# UV-Led.net
KiCad netlist of a schematic drawn in EAGLE
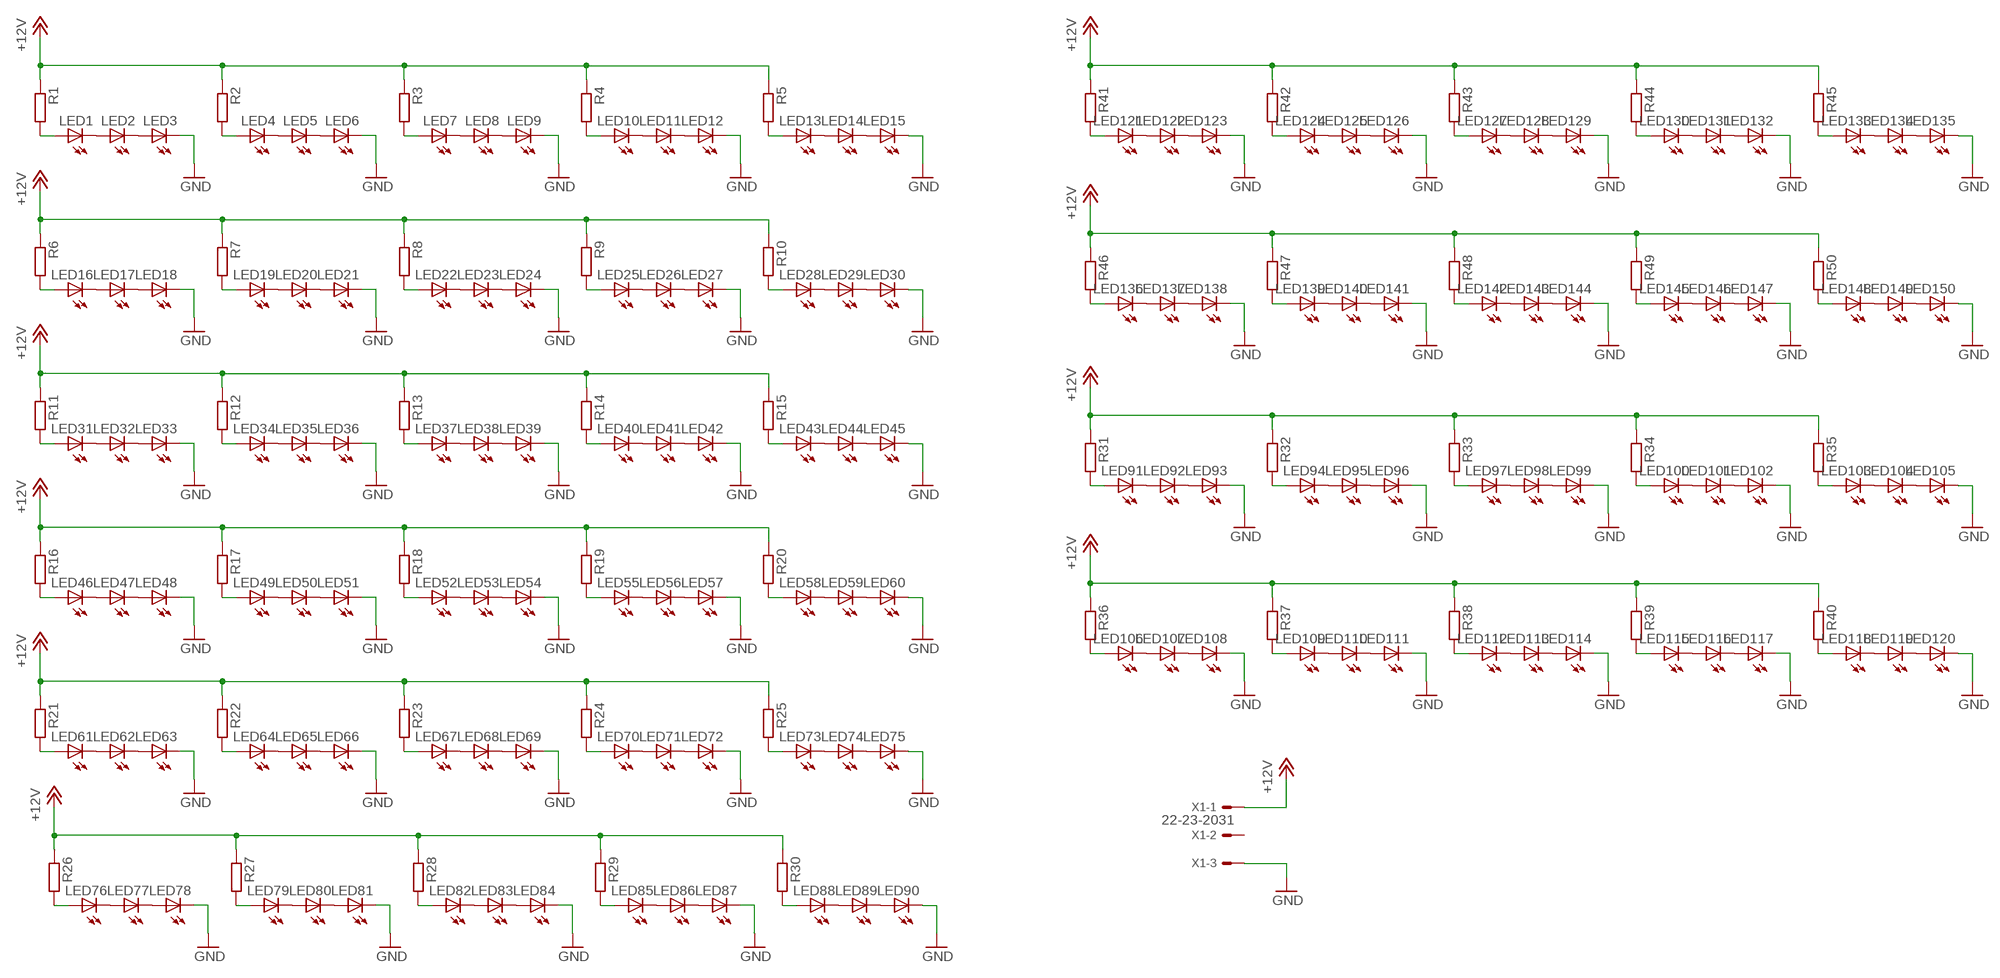
[diagram p0: schematic, sheet 1]

(export (version "E")
  (design (tool "Eeschema 10.0.6"))
  (components
    (comp (ref "LED1")
      (value "LED5MM")
      (footprint "eagle-import:LED5MM")
      (libsource (lib "eagle-import") (part "LED5MM"))
    )
    (comp (ref "LED2")
      (value "LED5MM")
      (footprint "eagle-import:LED5MM")
      (libsource (lib "eagle-import") (part "LED5MM"))
    )
    (comp (ref "LED3")
      (value "LED5MM")
      (footprint "eagle-import:LED5MM")
      (libsource (lib "eagle-import") (part "LED5MM"))
    )
    (comp (ref "LED4")
      (value "LED5MM")
      (footprint "eagle-import:LED5MM")
      (libsource (lib "eagle-import") (part "LED5MM"))
    )
    (comp (ref "LED5")
      (value "LED5MM")
      (footprint "eagle-import:LED5MM")
      (libsource (lib "eagle-import") (part "LED5MM"))
    )
    (comp (ref "LED6")
      (value "LED5MM")
      (footprint "eagle-import:LED5MM")
      (libsource (lib "eagle-import") (part "LED5MM"))
    )
    (comp (ref "LED7")
      (value "LED5MM")
      (footprint "eagle-import:LED5MM")
      (libsource (lib "eagle-import") (part "LED5MM"))
    )
    (comp (ref "LED8")
      (value "LED5MM")
      (footprint "eagle-import:LED5MM")
      (libsource (lib "eagle-import") (part "LED5MM"))
    )
    (comp (ref "LED9")
      (value "LED5MM")
      (footprint "eagle-import:LED5MM")
      (libsource (lib "eagle-import") (part "LED5MM"))
    )
    (comp (ref "LED10")
      (value "LED5MM")
      (footprint "eagle-import:LED5MM")
      (libsource (lib "eagle-import") (part "LED5MM"))
    )
    (comp (ref "LED11")
      (value "LED5MM")
      (footprint "eagle-import:LED5MM")
      (libsource (lib "eagle-import") (part "LED5MM"))
    )
    (comp (ref "LED12")
      (value "LED5MM")
      (footprint "eagle-import:LED5MM")
      (libsource (lib "eagle-import") (part "LED5MM"))
    )
    (comp (ref "LED13")
      (value "LED5MM")
      (footprint "eagle-import:LED5MM")
      (libsource (lib "eagle-import") (part "LED5MM"))
    )
    (comp (ref "LED14")
      (value "LED5MM")
      (footprint "eagle-import:LED5MM")
      (libsource (lib "eagle-import") (part "LED5MM"))
    )
    (comp (ref "LED15")
      (value "LED5MM")
      (footprint "eagle-import:LED5MM")
      (libsource (lib "eagle-import") (part "LED5MM"))
    )
    (comp (ref "LED16")
      (value "LED5MM")
      (footprint "eagle-import:LED5MM")
      (libsource (lib "eagle-import") (part "LED5MM"))
    )
    (comp (ref "LED17")
      (value "LED5MM")
      (footprint "eagle-import:LED5MM")
      (libsource (lib "eagle-import") (part "LED5MM"))
    )
    (comp (ref "LED18")
      (value "LED5MM")
      (footprint "eagle-import:LED5MM")
      (libsource (lib "eagle-import") (part "LED5MM"))
    )
    (comp (ref "LED19")
      (value "LED5MM")
      (footprint "eagle-import:LED5MM")
      (libsource (lib "eagle-import") (part "LED5MM"))
    )
    (comp (ref "LED20")
      (value "LED5MM")
      (footprint "eagle-import:LED5MM")
      (libsource (lib "eagle-import") (part "LED5MM"))
    )
    (comp (ref "LED21")
      (value "LED5MM")
      (footprint "eagle-import:LED5MM")
      (libsource (lib "eagle-import") (part "LED5MM"))
    )
    (comp (ref "LED22")
      (value "LED5MM")
      (footprint "eagle-import:LED5MM")
      (libsource (lib "eagle-import") (part "LED5MM"))
    )
    (comp (ref "LED23")
      (value "LED5MM")
      (footprint "eagle-import:LED5MM")
      (libsource (lib "eagle-import") (part "LED5MM"))
    )
    (comp (ref "LED24")
      (value "LED5MM")
      (footprint "eagle-import:LED5MM")
      (libsource (lib "eagle-import") (part "LED5MM"))
    )
    (comp (ref "LED25")
      (value "LED5MM")
      (footprint "eagle-import:LED5MM")
      (libsource (lib "eagle-import") (part "LED5MM"))
    )
    (comp (ref "LED26")
      (value "LED5MM")
      (footprint "eagle-import:LED5MM")
      (libsource (lib "eagle-import") (part "LED5MM"))
    )
    (comp (ref "LED27")
      (value "LED5MM")
      (footprint "eagle-import:LED5MM")
      (libsource (lib "eagle-import") (part "LED5MM"))
    )
    (comp (ref "LED28")
      (value "LED5MM")
      (footprint "eagle-import:LED5MM")
      (libsource (lib "eagle-import") (part "LED5MM"))
    )
    (comp (ref "LED29")
      (value "LED5MM")
      (footprint "eagle-import:LED5MM")
      (libsource (lib "eagle-import") (part "LED5MM"))
    )
    (comp (ref "LED30")
      (value "LED5MM")
      (footprint "eagle-import:LED5MM")
      (libsource (lib "eagle-import") (part "LED5MM"))
    )
    (comp (ref "LED31")
      (value "LED5MM")
      (footprint "eagle-import:LED5MM")
      (libsource (lib "eagle-import") (part "LED5MM"))
    )
    (comp (ref "LED32")
      (value "LED5MM")
      (footprint "eagle-import:LED5MM")
      (libsource (lib "eagle-import") (part "LED5MM"))
    )
    (comp (ref "LED33")
      (value "LED5MM")
      (footprint "eagle-import:LED5MM")
      (libsource (lib "eagle-import") (part "LED5MM"))
    )
    (comp (ref "LED34")
      (value "LED5MM")
      (footprint "eagle-import:LED5MM")
      (libsource (lib "eagle-import") (part "LED5MM"))
    )
    (comp (ref "LED35")
      (value "LED5MM")
      (footprint "eagle-import:LED5MM")
      (libsource (lib "eagle-import") (part "LED5MM"))
    )
    (comp (ref "LED36")
      (value "LED5MM")
      (footprint "eagle-import:LED5MM")
      (libsource (lib "eagle-import") (part "LED5MM"))
    )
    (comp (ref "LED37")
      (value "LED5MM")
      (footprint "eagle-import:LED5MM")
      (libsource (lib "eagle-import") (part "LED5MM"))
    )
    (comp (ref "LED38")
      (value "LED5MM")
      (footprint "eagle-import:LED5MM")
      (libsource (lib "eagle-import") (part "LED5MM"))
    )
    (comp (ref "LED39")
      (value "LED5MM")
      (footprint "eagle-import:LED5MM")
      (libsource (lib "eagle-import") (part "LED5MM"))
    )
    (comp (ref "LED40")
      (value "LED5MM")
      (footprint "eagle-import:LED5MM")
      (libsource (lib "eagle-import") (part "LED5MM"))
    )
    (comp (ref "LED41")
      (value "LED5MM")
      (footprint "eagle-import:LED5MM")
      (libsource (lib "eagle-import") (part "LED5MM"))
    )
    (comp (ref "LED42")
      (value "LED5MM")
      (footprint "eagle-import:LED5MM")
      (libsource (lib "eagle-import") (part "LED5MM"))
    )
    (comp (ref "LED43")
      (value "LED5MM")
      (footprint "eagle-import:LED5MM")
      (libsource (lib "eagle-import") (part "LED5MM"))
    )
    (comp (ref "LED44")
      (value "LED5MM")
      (footprint "eagle-import:LED5MM")
      (libsource (lib "eagle-import") (part "LED5MM"))
    )
    (comp (ref "LED45")
      (value "LED5MM")
      (footprint "eagle-import:LED5MM")
      (libsource (lib "eagle-import") (part "LED5MM"))
    )
    (comp (ref "LED46")
      (value "LED5MM")
      (footprint "eagle-import:LED5MM")
      (libsource (lib "eagle-import") (part "LED5MM"))
    )
    (comp (ref "LED47")
      (value "LED5MM")
      (footprint "eagle-import:LED5MM")
      (libsource (lib "eagle-import") (part "LED5MM"))
    )
    (comp (ref "LED48")
      (value "LED5MM")
      (footprint "eagle-import:LED5MM")
      (libsource (lib "eagle-import") (part "LED5MM"))
    )
    (comp (ref "LED49")
      (value "LED5MM")
      (footprint "eagle-import:LED5MM")
      (libsource (lib "eagle-import") (part "LED5MM"))
    )
    (comp (ref "LED50")
      (value "LED5MM")
      (footprint "eagle-import:LED5MM")
      (libsource (lib "eagle-import") (part "LED5MM"))
    )
    (comp (ref "LED51")
      (value "LED5MM")
      (footprint "eagle-import:LED5MM")
      (libsource (lib "eagle-import") (part "LED5MM"))
    )
    (comp (ref "LED52")
      (value "LED5MM")
      (footprint "eagle-import:LED5MM")
      (libsource (lib "eagle-import") (part "LED5MM"))
    )
    (comp (ref "LED53")
      (value "LED5MM")
      (footprint "eagle-import:LED5MM")
      (libsource (lib "eagle-import") (part "LED5MM"))
    )
    (comp (ref "LED54")
      (value "LED5MM")
      (footprint "eagle-import:LED5MM")
      (libsource (lib "eagle-import") (part "LED5MM"))
    )
    (comp (ref "LED55")
      (value "LED5MM")
      (footprint "eagle-import:LED5MM")
      (libsource (lib "eagle-import") (part "LED5MM"))
    )
    (comp (ref "LED56")
      (value "LED5MM")
      (footprint "eagle-import:LED5MM")
      (libsource (lib "eagle-import") (part "LED5MM"))
    )
    (comp (ref "LED57")
      (value "LED5MM")
      (footprint "eagle-import:LED5MM")
      (libsource (lib "eagle-import") (part "LED5MM"))
    )
    (comp (ref "LED58")
      (value "LED5MM")
      (footprint "eagle-import:LED5MM")
      (libsource (lib "eagle-import") (part "LED5MM"))
    )
    (comp (ref "LED59")
      (value "LED5MM")
      (footprint "eagle-import:LED5MM")
      (libsource (lib "eagle-import") (part "LED5MM"))
    )
    (comp (ref "LED60")
      (value "LED5MM")
      (footprint "eagle-import:LED5MM")
      (libsource (lib "eagle-import") (part "LED5MM"))
    )
    (comp (ref "LED61")
      (value "LED5MM")
      (footprint "eagle-import:LED5MM")
      (libsource (lib "eagle-import") (part "LED5MM"))
    )
    (comp (ref "LED62")
      (value "LED5MM")
      (footprint "eagle-import:LED5MM")
      (libsource (lib "eagle-import") (part "LED5MM"))
    )
    (comp (ref "LED63")
      (value "LED5MM")
      (footprint "eagle-import:LED5MM")
      (libsource (lib "eagle-import") (part "LED5MM"))
    )
    (comp (ref "LED64")
      (value "LED5MM")
      (footprint "eagle-import:LED5MM")
      (libsource (lib "eagle-import") (part "LED5MM"))
    )
    (comp (ref "LED65")
      (value "LED5MM")
      (footprint "eagle-import:LED5MM")
      (libsource (lib "eagle-import") (part "LED5MM"))
    )
    (comp (ref "LED66")
      (value "LED5MM")
      (footprint "eagle-import:LED5MM")
      (libsource (lib "eagle-import") (part "LED5MM"))
    )
    (comp (ref "LED67")
      (value "LED5MM")
      (footprint "eagle-import:LED5MM")
      (libsource (lib "eagle-import") (part "LED5MM"))
    )
    (comp (ref "LED68")
      (value "LED5MM")
      (footprint "eagle-import:LED5MM")
      (libsource (lib "eagle-import") (part "LED5MM"))
    )
    (comp (ref "LED69")
      (value "LED5MM")
      (footprint "eagle-import:LED5MM")
      (libsource (lib "eagle-import") (part "LED5MM"))
    )
    (comp (ref "LED70")
      (value "LED5MM")
      (footprint "eagle-import:LED5MM")
      (libsource (lib "eagle-import") (part "LED5MM"))
    )
    (comp (ref "LED71")
      (value "LED5MM")
      (footprint "eagle-import:LED5MM")
      (libsource (lib "eagle-import") (part "LED5MM"))
    )
    (comp (ref "LED72")
      (value "LED5MM")
      (footprint "eagle-import:LED5MM")
      (libsource (lib "eagle-import") (part "LED5MM"))
    )
    (comp (ref "LED73")
      (value "LED5MM")
      (footprint "eagle-import:LED5MM")
      (libsource (lib "eagle-import") (part "LED5MM"))
    )
    (comp (ref "LED74")
      (value "LED5MM")
      (footprint "eagle-import:LED5MM")
      (libsource (lib "eagle-import") (part "LED5MM"))
    )
    (comp (ref "LED75")
      (value "LED5MM")
      (footprint "eagle-import:LED5MM")
      (libsource (lib "eagle-import") (part "LED5MM"))
    )
    (comp (ref "LED76")
      (value "LED5MM")
      (footprint "eagle-import:LED5MM")
      (libsource (lib "eagle-import") (part "LED5MM"))
    )
    (comp (ref "LED77")
      (value "LED5MM")
      (footprint "eagle-import:LED5MM")
      (libsource (lib "eagle-import") (part "LED5MM"))
    )
    (comp (ref "LED78")
      (value "LED5MM")
      (footprint "eagle-import:LED5MM")
      (libsource (lib "eagle-import") (part "LED5MM"))
    )
    (comp (ref "LED79")
      (value "LED5MM")
      (footprint "eagle-import:LED5MM")
      (libsource (lib "eagle-import") (part "LED5MM"))
    )
    (comp (ref "LED80")
      (value "LED5MM")
      (footprint "eagle-import:LED5MM")
      (libsource (lib "eagle-import") (part "LED5MM"))
    )
    (comp (ref "LED81")
      (value "LED5MM")
      (footprint "eagle-import:LED5MM")
      (libsource (lib "eagle-import") (part "LED5MM"))
    )
    (comp (ref "LED82")
      (value "LED5MM")
      (footprint "eagle-import:LED5MM")
      (libsource (lib "eagle-import") (part "LED5MM"))
    )
    (comp (ref "LED83")
      (value "LED5MM")
      (footprint "eagle-import:LED5MM")
      (libsource (lib "eagle-import") (part "LED5MM"))
    )
    (comp (ref "LED84")
      (value "LED5MM")
      (footprint "eagle-import:LED5MM")
      (libsource (lib "eagle-import") (part "LED5MM"))
    )
    (comp (ref "LED85")
      (value "LED5MM")
      (footprint "eagle-import:LED5MM")
      (libsource (lib "eagle-import") (part "LED5MM"))
    )
    (comp (ref "LED86")
      (value "LED5MM")
      (footprint "eagle-import:LED5MM")
      (libsource (lib "eagle-import") (part "LED5MM"))
    )
    (comp (ref "LED87")
      (value "LED5MM")
      (footprint "eagle-import:LED5MM")
      (libsource (lib "eagle-import") (part "LED5MM"))
    )
    (comp (ref "LED88")
      (value "LED5MM")
      (footprint "eagle-import:LED5MM")
      (libsource (lib "eagle-import") (part "LED5MM"))
    )
    (comp (ref "LED89")
      (value "LED5MM")
      (footprint "eagle-import:LED5MM")
      (libsource (lib "eagle-import") (part "LED5MM"))
    )
    (comp (ref "LED90")
      (value "LED5MM")
      (footprint "eagle-import:LED5MM")
      (libsource (lib "eagle-import") (part "LED5MM"))
    )
    (comp (ref "LED91")
      (value "LED5MM")
      (footprint "eagle-import:LED5MM")
      (libsource (lib "eagle-import") (part "LED5MM"))
    )
    (comp (ref "LED92")
      (value "LED5MM")
      (footprint "eagle-import:LED5MM")
      (libsource (lib "eagle-import") (part "LED5MM"))
    )
    (comp (ref "LED93")
      (value "LED5MM")
      (footprint "eagle-import:LED5MM")
      (libsource (lib "eagle-import") (part "LED5MM"))
    )
    (comp (ref "LED94")
      (value "LED5MM")
      (footprint "eagle-import:LED5MM")
      (libsource (lib "eagle-import") (part "LED5MM"))
    )
    (comp (ref "LED95")
      (value "LED5MM")
      (footprint "eagle-import:LED5MM")
      (libsource (lib "eagle-import") (part "LED5MM"))
    )
    (comp (ref "LED96")
      (value "LED5MM")
      (footprint "eagle-import:LED5MM")
      (libsource (lib "eagle-import") (part "LED5MM"))
    )
    (comp (ref "LED97")
      (value "LED5MM")
      (footprint "eagle-import:LED5MM")
      (libsource (lib "eagle-import") (part "LED5MM"))
    )
    (comp (ref "LED98")
      (value "LED5MM")
      (footprint "eagle-import:LED5MM")
      (libsource (lib "eagle-import") (part "LED5MM"))
    )
    (comp (ref "LED99")
      (value "LED5MM")
      (footprint "eagle-import:LED5MM")
      (libsource (lib "eagle-import") (part "LED5MM"))
    )
    (comp (ref "LED100")
      (value "LED5MM")
      (footprint "eagle-import:LED5MM")
      (libsource (lib "eagle-import") (part "LED5MM"))
    )
    (comp (ref "LED101")
      (value "LED5MM")
      (footprint "eagle-import:LED5MM")
      (libsource (lib "eagle-import") (part "LED5MM"))
    )
    (comp (ref "LED102")
      (value "LED5MM")
      (footprint "eagle-import:LED5MM")
      (libsource (lib "eagle-import") (part "LED5MM"))
    )
    (comp (ref "LED103")
      (value "LED5MM")
      (footprint "eagle-import:LED5MM")
      (libsource (lib "eagle-import") (part "LED5MM"))
    )
    (comp (ref "LED104")
      (value "LED5MM")
      (footprint "eagle-import:LED5MM")
      (libsource (lib "eagle-import") (part "LED5MM"))
    )
    (comp (ref "LED105")
      (value "LED5MM")
      (footprint "eagle-import:LED5MM")
      (libsource (lib "eagle-import") (part "LED5MM"))
    )
    (comp (ref "LED106")
      (value "LED5MM")
      (footprint "eagle-import:LED5MM")
      (libsource (lib "eagle-import") (part "LED5MM"))
    )
    (comp (ref "LED107")
      (value "LED5MM")
      (footprint "eagle-import:LED5MM")
      (libsource (lib "eagle-import") (part "LED5MM"))
    )
    (comp (ref "LED108")
      (value "LED5MM")
      (footprint "eagle-import:LED5MM")
      (libsource (lib "eagle-import") (part "LED5MM"))
    )
    (comp (ref "LED109")
      (value "LED5MM")
      (footprint "eagle-import:LED5MM")
      (libsource (lib "eagle-import") (part "LED5MM"))
    )
    (comp (ref "LED110")
      (value "LED5MM")
      (footprint "eagle-import:LED5MM")
      (libsource (lib "eagle-import") (part "LED5MM"))
    )
    (comp (ref "LED111")
      (value "LED5MM")
      (footprint "eagle-import:LED5MM")
      (libsource (lib "eagle-import") (part "LED5MM"))
    )
    (comp (ref "LED112")
      (value "LED5MM")
      (footprint "eagle-import:LED5MM")
      (libsource (lib "eagle-import") (part "LED5MM"))
    )
    (comp (ref "LED113")
      (value "LED5MM")
      (footprint "eagle-import:LED5MM")
      (libsource (lib "eagle-import") (part "LED5MM"))
    )
    (comp (ref "LED114")
      (value "LED5MM")
      (footprint "eagle-import:LED5MM")
      (libsource (lib "eagle-import") (part "LED5MM"))
    )
    (comp (ref "LED115")
      (value "LED5MM")
      (footprint "eagle-import:LED5MM")
      (libsource (lib "eagle-import") (part "LED5MM"))
    )
    (comp (ref "LED116")
      (value "LED5MM")
      (footprint "eagle-import:LED5MM")
      (libsource (lib "eagle-import") (part "LED5MM"))
    )
    (comp (ref "LED117")
      (value "LED5MM")
      (footprint "eagle-import:LED5MM")
      (libsource (lib "eagle-import") (part "LED5MM"))
    )
    (comp (ref "LED118")
      (value "LED5MM")
      (footprint "eagle-import:LED5MM")
      (libsource (lib "eagle-import") (part "LED5MM"))
    )
    (comp (ref "LED119")
      (value "LED5MM")
      (footprint "eagle-import:LED5MM")
      (libsource (lib "eagle-import") (part "LED5MM"))
    )
    (comp (ref "LED120")
      (value "LED5MM")
      (footprint "eagle-import:LED5MM")
      (libsource (lib "eagle-import") (part "LED5MM"))
    )
    (comp (ref "LED121")
      (value "LED5MM")
      (footprint "eagle-import:LED5MM")
      (libsource (lib "eagle-import") (part "LED5MM"))
    )
    (comp (ref "LED122")
      (value "LED5MM")
      (footprint "eagle-import:LED5MM")
      (libsource (lib "eagle-import") (part "LED5MM"))
    )
    (comp (ref "LED123")
      (value "LED5MM")
      (footprint "eagle-import:LED5MM")
      (libsource (lib "eagle-import") (part "LED5MM"))
    )
    (comp (ref "LED124")
      (value "LED5MM")
      (footprint "eagle-import:LED5MM")
      (libsource (lib "eagle-import") (part "LED5MM"))
    )
    (comp (ref "LED125")
      (value "LED5MM")
      (footprint "eagle-import:LED5MM")
      (libsource (lib "eagle-import") (part "LED5MM"))
    )
    (comp (ref "LED126")
      (value "LED5MM")
      (footprint "eagle-import:LED5MM")
      (libsource (lib "eagle-import") (part "LED5MM"))
    )
    (comp (ref "LED127")
      (value "LED5MM")
      (footprint "eagle-import:LED5MM")
      (libsource (lib "eagle-import") (part "LED5MM"))
    )
    (comp (ref "LED128")
      (value "LED5MM")
      (footprint "eagle-import:LED5MM")
      (libsource (lib "eagle-import") (part "LED5MM"))
    )
    (comp (ref "LED129")
      (value "LED5MM")
      (footprint "eagle-import:LED5MM")
      (libsource (lib "eagle-import") (part "LED5MM"))
    )
    (comp (ref "LED130")
      (value "LED5MM")
      (footprint "eagle-import:LED5MM")
      (libsource (lib "eagle-import") (part "LED5MM"))
    )
    (comp (ref "LED131")
      (value "LED5MM")
      (footprint "eagle-import:LED5MM")
      (libsource (lib "eagle-import") (part "LED5MM"))
    )
    (comp (ref "LED132")
      (value "LED5MM")
      (footprint "eagle-import:LED5MM")
      (libsource (lib "eagle-import") (part "LED5MM"))
    )
    (comp (ref "LED133")
      (value "LED5MM")
      (footprint "eagle-import:LED5MM")
      (libsource (lib "eagle-import") (part "LED5MM"))
    )
    (comp (ref "LED134")
      (value "LED5MM")
      (footprint "eagle-import:LED5MM")
      (libsource (lib "eagle-import") (part "LED5MM"))
    )
    (comp (ref "LED135")
      (value "LED5MM")
      (footprint "eagle-import:LED5MM")
      (libsource (lib "eagle-import") (part "LED5MM"))
    )
    (comp (ref "LED136")
      (value "LED5MM")
      (footprint "eagle-import:LED5MM")
      (libsource (lib "eagle-import") (part "LED5MM"))
    )
    (comp (ref "LED137")
      (value "LED5MM")
      (footprint "eagle-import:LED5MM")
      (libsource (lib "eagle-import") (part "LED5MM"))
    )
    (comp (ref "LED138")
      (value "LED5MM")
      (footprint "eagle-import:LED5MM")
      (libsource (lib "eagle-import") (part "LED5MM"))
    )
    (comp (ref "LED139")
      (value "LED5MM")
      (footprint "eagle-import:LED5MM")
      (libsource (lib "eagle-import") (part "LED5MM"))
    )
    (comp (ref "LED140")
      (value "LED5MM")
      (footprint "eagle-import:LED5MM")
      (libsource (lib "eagle-import") (part "LED5MM"))
    )
    (comp (ref "LED141")
      (value "LED5MM")
      (footprint "eagle-import:LED5MM")
      (libsource (lib "eagle-import") (part "LED5MM"))
    )
    (comp (ref "LED142")
      (value "LED5MM")
      (footprint "eagle-import:LED5MM")
      (libsource (lib "eagle-import") (part "LED5MM"))
    )
    (comp (ref "LED143")
      (value "LED5MM")
      (footprint "eagle-import:LED5MM")
      (libsource (lib "eagle-import") (part "LED5MM"))
    )
    (comp (ref "LED144")
      (value "LED5MM")
      (footprint "eagle-import:LED5MM")
      (libsource (lib "eagle-import") (part "LED5MM"))
    )
    (comp (ref "LED145")
      (value "LED5MM")
      (footprint "eagle-import:LED5MM")
      (libsource (lib "eagle-import") (part "LED5MM"))
    )
    (comp (ref "LED146")
      (value "LED5MM")
      (footprint "eagle-import:LED5MM")
      (libsource (lib "eagle-import") (part "LED5MM"))
    )
    (comp (ref "LED147")
      (value "LED5MM")
      (footprint "eagle-import:LED5MM")
      (libsource (lib "eagle-import") (part "LED5MM"))
    )
    (comp (ref "LED148")
      (value "LED5MM")
      (footprint "eagle-import:LED5MM")
      (libsource (lib "eagle-import") (part "LED5MM"))
    )
    (comp (ref "LED149")
      (value "LED5MM")
      (footprint "eagle-import:LED5MM")
      (libsource (lib "eagle-import") (part "LED5MM"))
    )
    (comp (ref "LED150")
      (value "LED5MM")
      (footprint "eagle-import:LED5MM")
      (libsource (lib "eagle-import") (part "LED5MM"))
    )
    (comp (ref "R1")
      (value "R-EU_0207/10")
      (footprint "eagle-import:0207_10")
      (libsource (lib "eagle-import") (part "R-EU_0207/10"))
    )
    (comp (ref "R2")
      (value "R-EU_0207/10")
      (footprint "eagle-import:0207_10")
      (libsource (lib "eagle-import") (part "R-EU_0207/10"))
    )
    (comp (ref "R3")
      (value "R-EU_0207/10")
      (footprint "eagle-import:0207_10")
      (libsource (lib "eagle-import") (part "R-EU_0207/10"))
    )
    (comp (ref "R4")
      (value "R-EU_0207/10")
      (footprint "eagle-import:0207_10")
      (libsource (lib "eagle-import") (part "R-EU_0207/10"))
    )
    (comp (ref "R5")
      (value "R-EU_0207/10")
      (footprint "eagle-import:0207_10")
      (libsource (lib "eagle-import") (part "R-EU_0207/10"))
    )
    (comp (ref "R6")
      (value "R-EU_0207/10")
      (footprint "eagle-import:0207_10")
      (libsource (lib "eagle-import") (part "R-EU_0207/10"))
    )
    (comp (ref "R7")
      (value "R-EU_0207/10")
      (footprint "eagle-import:0207_10")
      (libsource (lib "eagle-import") (part "R-EU_0207/10"))
    )
    (comp (ref "R8")
      (value "R-EU_0207/10")
      (footprint "eagle-import:0207_10")
      (libsource (lib "eagle-import") (part "R-EU_0207/10"))
    )
    (comp (ref "R9")
      (value "R-EU_0207/10")
      (footprint "eagle-import:0207_10")
      (libsource (lib "eagle-import") (part "R-EU_0207/10"))
    )
    (comp (ref "R10")
      (value "R-EU_0207/10")
      (footprint "eagle-import:0207_10")
      (libsource (lib "eagle-import") (part "R-EU_0207/10"))
    )
    (comp (ref "R11")
      (value "R-EU_0207/10")
      (footprint "eagle-import:0207_10")
      (libsource (lib "eagle-import") (part "R-EU_0207/10"))
    )
    (comp (ref "R12")
      (value "R-EU_0207/10")
      (footprint "eagle-import:0207_10")
      (libsource (lib "eagle-import") (part "R-EU_0207/10"))
    )
    (comp (ref "R13")
      (value "R-EU_0207/10")
      (footprint "eagle-import:0207_10")
      (libsource (lib "eagle-import") (part "R-EU_0207/10"))
    )
    (comp (ref "R14")
      (value "R-EU_0207/10")
      (footprint "eagle-import:0207_10")
      (libsource (lib "eagle-import") (part "R-EU_0207/10"))
    )
    (comp (ref "R15")
      (value "R-EU_0207/10")
      (footprint "eagle-import:0207_10")
      (libsource (lib "eagle-import") (part "R-EU_0207/10"))
    )
    (comp (ref "R16")
      (value "R-EU_0207/10")
      (footprint "eagle-import:0207_10")
      (libsource (lib "eagle-import") (part "R-EU_0207/10"))
    )
    (comp (ref "R17")
      (value "R-EU_0207/10")
      (footprint "eagle-import:0207_10")
      (libsource (lib "eagle-import") (part "R-EU_0207/10"))
    )
    (comp (ref "R18")
      (value "R-EU_0207/10")
      (footprint "eagle-import:0207_10")
      (libsource (lib "eagle-import") (part "R-EU_0207/10"))
    )
    (comp (ref "R19")
      (value "R-EU_0207/10")
      (footprint "eagle-import:0207_10")
      (libsource (lib "eagle-import") (part "R-EU_0207/10"))
    )
    (comp (ref "R20")
      (value "R-EU_0207/10")
      (footprint "eagle-import:0207_10")
      (libsource (lib "eagle-import") (part "R-EU_0207/10"))
    )
    (comp (ref "R21")
      (value "R-EU_0207/10")
      (footprint "eagle-import:0207_10")
      (libsource (lib "eagle-import") (part "R-EU_0207/10"))
    )
    (comp (ref "R22")
      (value "R-EU_0207/10")
      (footprint "eagle-import:0207_10")
      (libsource (lib "eagle-import") (part "R-EU_0207/10"))
    )
    (comp (ref "R23")
      (value "R-EU_0207/10")
      (footprint "eagle-import:0207_10")
      (libsource (lib "eagle-import") (part "R-EU_0207/10"))
    )
    (comp (ref "R24")
      (value "R-EU_0207/10")
      (footprint "eagle-import:0207_10")
      (libsource (lib "eagle-import") (part "R-EU_0207/10"))
    )
    (comp (ref "R25")
      (value "R-EU_0207/10")
      (footprint "eagle-import:0207_10")
      (libsource (lib "eagle-import") (part "R-EU_0207/10"))
    )
    (comp (ref "R26")
      (value "R-EU_0207/10")
      (footprint "eagle-import:0207_10")
      (libsource (lib "eagle-import") (part "R-EU_0207/10"))
    )
    (comp (ref "R27")
      (value "R-EU_0207/10")
      (footprint "eagle-import:0207_10")
      (libsource (lib "eagle-import") (part "R-EU_0207/10"))
    )
    (comp (ref "R28")
      (value "R-EU_0207/10")
      (footprint "eagle-import:0207_10")
      (libsource (lib "eagle-import") (part "R-EU_0207/10"))
    )
    (comp (ref "R29")
      (value "R-EU_0207/10")
      (footprint "eagle-import:0207_10")
      (libsource (lib "eagle-import") (part "R-EU_0207/10"))
    )
    (comp (ref "R30")
      (value "R-EU_0207/10")
      (footprint "eagle-import:0207_10")
      (libsource (lib "eagle-import") (part "R-EU_0207/10"))
    )
    (comp (ref "R31")
      (value "R-EU_0207/10")
      (footprint "eagle-import:0207_10")
      (libsource (lib "eagle-import") (part "R-EU_0207/10"))
    )
    (comp (ref "R32")
      (value "R-EU_0207/10")
      (footprint "eagle-import:0207_10")
      (libsource (lib "eagle-import") (part "R-EU_0207/10"))
    )
    (comp (ref "R33")
      (value "R-EU_0207/10")
      (footprint "eagle-import:0207_10")
      (libsource (lib "eagle-import") (part "R-EU_0207/10"))
    )
    (comp (ref "R34")
      (value "R-EU_0207/10")
      (footprint "eagle-import:0207_10")
      (libsource (lib "eagle-import") (part "R-EU_0207/10"))
    )
    (comp (ref "R35")
      (value "R-EU_0207/10")
      (footprint "eagle-import:0207_10")
      (libsource (lib "eagle-import") (part "R-EU_0207/10"))
    )
    (comp (ref "R36")
      (value "R-EU_0207/10")
      (footprint "eagle-import:0207_10")
      (libsource (lib "eagle-import") (part "R-EU_0207/10"))
    )
    (comp (ref "R37")
      (value "R-EU_0207/10")
      (footprint "eagle-import:0207_10")
      (libsource (lib "eagle-import") (part "R-EU_0207/10"))
    )
    (comp (ref "R38")
      (value "R-EU_0207/10")
      (footprint "eagle-import:0207_10")
      (libsource (lib "eagle-import") (part "R-EU_0207/10"))
    )
    (comp (ref "R39")
      (value "R-EU_0207/10")
      (footprint "eagle-import:0207_10")
      (libsource (lib "eagle-import") (part "R-EU_0207/10"))
    )
    (comp (ref "R40")
      (value "R-EU_0207/10")
      (footprint "eagle-import:0207_10")
      (libsource (lib "eagle-import") (part "R-EU_0207/10"))
    )
    (comp (ref "R41")
      (value "R-EU_0207/10")
      (footprint "eagle-import:0207_10")
      (libsource (lib "eagle-import") (part "R-EU_0207/10"))
    )
    (comp (ref "R42")
      (value "R-EU_0207/10")
      (footprint "eagle-import:0207_10")
      (libsource (lib "eagle-import") (part "R-EU_0207/10"))
    )
    (comp (ref "R43")
      (value "R-EU_0207/10")
      (footprint "eagle-import:0207_10")
      (libsource (lib "eagle-import") (part "R-EU_0207/10"))
    )
    (comp (ref "R44")
      (value "R-EU_0207/10")
      (footprint "eagle-import:0207_10")
      (libsource (lib "eagle-import") (part "R-EU_0207/10"))
    )
    (comp (ref "R45")
      (value "R-EU_0207/10")
      (footprint "eagle-import:0207_10")
      (libsource (lib "eagle-import") (part "R-EU_0207/10"))
    )
    (comp (ref "R46")
      (value "R-EU_0207/10")
      (footprint "eagle-import:0207_10")
      (libsource (lib "eagle-import") (part "R-EU_0207/10"))
    )
    (comp (ref "R47")
      (value "R-EU_0207/10")
      (footprint "eagle-import:0207_10")
      (libsource (lib "eagle-import") (part "R-EU_0207/10"))
    )
    (comp (ref "R48")
      (value "R-EU_0207/10")
      (footprint "eagle-import:0207_10")
      (libsource (lib "eagle-import") (part "R-EU_0207/10"))
    )
    (comp (ref "R49")
      (value "R-EU_0207/10")
      (footprint "eagle-import:0207_10")
      (libsource (lib "eagle-import") (part "R-EU_0207/10"))
    )
    (comp (ref "R50")
      (value "R-EU_0207/10")
      (footprint "eagle-import:0207_10")
      (libsource (lib "eagle-import") (part "R-EU_0207/10"))
    )
    (comp (ref "X1")
      (value "22-23-2031")
      (footprint "eagle-import:22-23-2031")
      (fields (field (name "MF") "MOLEX"))
      (libsource (lib "eagle-import") (part "22-23-2031"))
    )
  )
  (nets
    (net (code "1") (name "+12V") (class "Default")
      (node (ref "R1") (pin "1") (pinfunction "1_1") (pintype "passive"))
      (node (ref "R10") (pin "1") (pinfunction "1_1") (pintype "passive"))
      (node (ref "R11") (pin "1") (pinfunction "1_1") (pintype "passive"))
      (node (ref "R12") (pin "1") (pinfunction "1_1") (pintype "passive"))
      (node (ref "R13") (pin "1") (pinfunction "1_1") (pintype "passive"))
      (node (ref "R14") (pin "1") (pinfunction "1_1") (pintype "passive"))
      (node (ref "R15") (pin "1") (pinfunction "1_1") (pintype "passive"))
      (node (ref "R16") (pin "1") (pinfunction "1_1") (pintype "passive"))
      (node (ref "R17") (pin "1") (pinfunction "1_1") (pintype "passive"))
      (node (ref "R18") (pin "1") (pinfunction "1_1") (pintype "passive"))
      (node (ref "R19") (pin "1") (pinfunction "1_1") (pintype "passive"))
      (node (ref "R2") (pin "1") (pinfunction "1_1") (pintype "passive"))
      (node (ref "R20") (pin "1") (pinfunction "1_1") (pintype "passive"))
      (node (ref "R21") (pin "1") (pinfunction "1_1") (pintype "passive"))
      (node (ref "R22") (pin "1") (pinfunction "1_1") (pintype "passive"))
      (node (ref "R23") (pin "1") (pinfunction "1_1") (pintype "passive"))
      (node (ref "R24") (pin "1") (pinfunction "1_1") (pintype "passive"))
      (node (ref "R25") (pin "1") (pinfunction "1_1") (pintype "passive"))
      (node (ref "R26") (pin "1") (pinfunction "1_1") (pintype "passive"))
      (node (ref "R27") (pin "1") (pinfunction "1_1") (pintype "passive"))
      (node (ref "R28") (pin "1") (pinfunction "1_1") (pintype "passive"))
      (node (ref "R29") (pin "1") (pinfunction "1_1") (pintype "passive"))
      (node (ref "R3") (pin "1") (pinfunction "1_1") (pintype "passive"))
      (node (ref "R30") (pin "1") (pinfunction "1_1") (pintype "passive"))
      (node (ref "R31") (pin "1") (pinfunction "1_1") (pintype "passive"))
      (node (ref "R32") (pin "1") (pinfunction "1_1") (pintype "passive"))
      (node (ref "R33") (pin "1") (pinfunction "1_1") (pintype "passive"))
      (node (ref "R34") (pin "1") (pinfunction "1_1") (pintype "passive"))
      (node (ref "R35") (pin "1") (pinfunction "1_1") (pintype "passive"))
      (node (ref "R36") (pin "1") (pinfunction "1_1") (pintype "passive"))
      (node (ref "R37") (pin "1") (pinfunction "1_1") (pintype "passive"))
      (node (ref "R38") (pin "1") (pinfunction "1_1") (pintype "passive"))
      (node (ref "R39") (pin "1") (pinfunction "1_1") (pintype "passive"))
      (node (ref "R4") (pin "1") (pinfunction "1_1") (pintype "passive"))
      (node (ref "R40") (pin "1") (pinfunction "1_1") (pintype "passive"))
      (node (ref "R41") (pin "1") (pinfunction "1_1") (pintype "passive"))
      (node (ref "R42") (pin "1") (pinfunction "1_1") (pintype "passive"))
      (node (ref "R43") (pin "1") (pinfunction "1_1") (pintype "passive"))
      (node (ref "R44") (pin "1") (pinfunction "1_1") (pintype "passive"))
      (node (ref "R45") (pin "1") (pinfunction "1_1") (pintype "passive"))
      (node (ref "R46") (pin "1") (pinfunction "1_1") (pintype "passive"))
      (node (ref "R47") (pin "1") (pinfunction "1_1") (pintype "passive"))
      (node (ref "R48") (pin "1") (pinfunction "1_1") (pintype "passive"))
      (node (ref "R49") (pin "1") (pinfunction "1_1") (pintype "passive"))
      (node (ref "R5") (pin "1") (pinfunction "1_1") (pintype "passive"))
      (node (ref "R50") (pin "1") (pinfunction "1_1") (pintype "passive"))
      (node (ref "R6") (pin "1") (pinfunction "1_1") (pintype "passive"))
      (node (ref "R7") (pin "1") (pinfunction "1_1") (pintype "passive"))
      (node (ref "R8") (pin "1") (pinfunction "1_1") (pintype "passive"))
      (node (ref "R9") (pin "1") (pinfunction "1_1") (pintype "passive"))
      (node (ref "X1") (pin "1") (pinfunction "S_1") (pintype "passive"))
    )
    (net (code "2") (name "GND") (class "Default")
      (node (ref "LED102") (pin "K") (pinfunction "C_K") (pintype "passive"))
      (node (ref "LED105") (pin "K") (pinfunction "C_K") (pintype "passive"))
      (node (ref "LED108") (pin "K") (pinfunction "C_K") (pintype "passive"))
      (node (ref "LED111") (pin "K") (pinfunction "C_K") (pintype "passive"))
      (node (ref "LED114") (pin "K") (pinfunction "C_K") (pintype "passive"))
      (node (ref "LED117") (pin "K") (pinfunction "C_K") (pintype "passive"))
      (node (ref "LED12") (pin "K") (pinfunction "C_K") (pintype "passive"))
      (node (ref "LED120") (pin "K") (pinfunction "C_K") (pintype "passive"))
      (node (ref "LED123") (pin "K") (pinfunction "C_K") (pintype "passive"))
      (node (ref "LED126") (pin "K") (pinfunction "C_K") (pintype "passive"))
      (node (ref "LED129") (pin "K") (pinfunction "C_K") (pintype "passive"))
      (node (ref "LED132") (pin "K") (pinfunction "C_K") (pintype "passive"))
      (node (ref "LED135") (pin "K") (pinfunction "C_K") (pintype "passive"))
      (node (ref "LED138") (pin "K") (pinfunction "C_K") (pintype "passive"))
      (node (ref "LED141") (pin "K") (pinfunction "C_K") (pintype "passive"))
      (node (ref "LED144") (pin "K") (pinfunction "C_K") (pintype "passive"))
      (node (ref "LED147") (pin "K") (pinfunction "C_K") (pintype "passive"))
      (node (ref "LED15") (pin "K") (pinfunction "C_K") (pintype "passive"))
      (node (ref "LED150") (pin "K") (pinfunction "C_K") (pintype "passive"))
      (node (ref "LED18") (pin "K") (pinfunction "C_K") (pintype "passive"))
      (node (ref "LED21") (pin "K") (pinfunction "C_K") (pintype "passive"))
      (node (ref "LED24") (pin "K") (pinfunction "C_K") (pintype "passive"))
      (node (ref "LED27") (pin "K") (pinfunction "C_K") (pintype "passive"))
      (node (ref "LED3") (pin "K") (pinfunction "C_K") (pintype "passive"))
      (node (ref "LED30") (pin "K") (pinfunction "C_K") (pintype "passive"))
      (node (ref "LED33") (pin "K") (pinfunction "C_K") (pintype "passive"))
      (node (ref "LED36") (pin "K") (pinfunction "C_K") (pintype "passive"))
      (node (ref "LED39") (pin "K") (pinfunction "C_K") (pintype "passive"))
      (node (ref "LED42") (pin "K") (pinfunction "C_K") (pintype "passive"))
      (node (ref "LED45") (pin "K") (pinfunction "C_K") (pintype "passive"))
      (node (ref "LED48") (pin "K") (pinfunction "C_K") (pintype "passive"))
      (node (ref "LED51") (pin "K") (pinfunction "C_K") (pintype "passive"))
      (node (ref "LED54") (pin "K") (pinfunction "C_K") (pintype "passive"))
      (node (ref "LED57") (pin "K") (pinfunction "C_K") (pintype "passive"))
      (node (ref "LED6") (pin "K") (pinfunction "C_K") (pintype "passive"))
      (node (ref "LED60") (pin "K") (pinfunction "C_K") (pintype "passive"))
      (node (ref "LED63") (pin "K") (pinfunction "C_K") (pintype "passive"))
      (node (ref "LED66") (pin "K") (pinfunction "C_K") (pintype "passive"))
      (node (ref "LED69") (pin "K") (pinfunction "C_K") (pintype "passive"))
      (node (ref "LED72") (pin "K") (pinfunction "C_K") (pintype "passive"))
      (node (ref "LED75") (pin "K") (pinfunction "C_K") (pintype "passive"))
      (node (ref "LED78") (pin "K") (pinfunction "C_K") (pintype "passive"))
      (node (ref "LED81") (pin "K") (pinfunction "C_K") (pintype "passive"))
      (node (ref "LED84") (pin "K") (pinfunction "C_K") (pintype "passive"))
      (node (ref "LED87") (pin "K") (pinfunction "C_K") (pintype "passive"))
      (node (ref "LED9") (pin "K") (pinfunction "C_K") (pintype "passive"))
      (node (ref "LED90") (pin "K") (pinfunction "C_K") (pintype "passive"))
      (node (ref "LED93") (pin "K") (pinfunction "C_K") (pintype "passive"))
      (node (ref "LED96") (pin "K") (pinfunction "C_K") (pintype "passive"))
      (node (ref "LED99") (pin "K") (pinfunction "C_K") (pintype "passive"))
      (node (ref "X1") (pin "3") (pinfunction "S_3") (pintype "passive"))
    )
    (net (code "3") (name "Net-(LED1-C)") (class "Default")
      (node (ref "LED1") (pin "K") (pinfunction "C_K") (pintype "passive"))
      (node (ref "LED2") (pin "A") (pinfunction "A_A") (pintype "passive"))
    )
    (net (code "4") (name "Net-(LED1-PadA)") (class "Default")
      (node (ref "LED1") (pin "A") (pinfunction "A_A") (pintype "passive"))
      (node (ref "R1") (pin "2") (pinfunction "2_2") (pintype "passive"))
    )
    (net (code "5") (name "Net-(LED2-C)") (class "Default")
      (node (ref "LED2") (pin "K") (pinfunction "C_K") (pintype "passive"))
      (node (ref "LED3") (pin "A") (pinfunction "A_A") (pintype "passive"))
    )
    (net (code "6") (name "Net-(LED4-C)") (class "Default")
      (node (ref "LED4") (pin "K") (pinfunction "C_K") (pintype "passive"))
      (node (ref "LED5") (pin "A") (pinfunction "A_A") (pintype "passive"))
    )
    (net (code "7") (name "Net-(LED4-PadA)") (class "Default")
      (node (ref "LED4") (pin "A") (pinfunction "A_A") (pintype "passive"))
      (node (ref "R2") (pin "2") (pinfunction "2_2") (pintype "passive"))
    )
    (net (code "8") (name "Net-(LED5-C)") (class "Default")
      (node (ref "LED5") (pin "K") (pinfunction "C_K") (pintype "passive"))
      (node (ref "LED6") (pin "A") (pinfunction "A_A") (pintype "passive"))
    )
    (net (code "9") (name "Net-(LED7-C)") (class "Default")
      (node (ref "LED7") (pin "K") (pinfunction "C_K") (pintype "passive"))
      (node (ref "LED8") (pin "A") (pinfunction "A_A") (pintype "passive"))
    )
    (net (code "10") (name "Net-(LED7-PadA)") (class "Default")
      (node (ref "LED7") (pin "A") (pinfunction "A_A") (pintype "passive"))
      (node (ref "R3") (pin "2") (pinfunction "2_2") (pintype "passive"))
    )
    (net (code "11") (name "Net-(LED8-C)") (class "Default")
      (node (ref "LED8") (pin "K") (pinfunction "C_K") (pintype "passive"))
      (node (ref "LED9") (pin "A") (pinfunction "A_A") (pintype "passive"))
    )
    (net (code "12") (name "Net-(LED10-C)") (class "Default")
      (node (ref "LED10") (pin "K") (pinfunction "C_K") (pintype "passive"))
      (node (ref "LED11") (pin "A") (pinfunction "A_A") (pintype "passive"))
    )
    (net (code "13") (name "Net-(LED10-PadA)") (class "Default")
      (node (ref "LED10") (pin "A") (pinfunction "A_A") (pintype "passive"))
      (node (ref "R4") (pin "2") (pinfunction "2_2") (pintype "passive"))
    )
    (net (code "14") (name "Net-(LED11-C)") (class "Default")
      (node (ref "LED11") (pin "K") (pinfunction "C_K") (pintype "passive"))
      (node (ref "LED12") (pin "A") (pinfunction "A_A") (pintype "passive"))
    )
    (net (code "15") (name "Net-(LED13-C)") (class "Default")
      (node (ref "LED13") (pin "K") (pinfunction "C_K") (pintype "passive"))
      (node (ref "LED14") (pin "A") (pinfunction "A_A") (pintype "passive"))
    )
    (net (code "16") (name "Net-(LED13-PadA)") (class "Default")
      (node (ref "LED13") (pin "A") (pinfunction "A_A") (pintype "passive"))
      (node (ref "R5") (pin "2") (pinfunction "2_2") (pintype "passive"))
    )
    (net (code "17") (name "Net-(LED14-C)") (class "Default")
      (node (ref "LED14") (pin "K") (pinfunction "C_K") (pintype "passive"))
      (node (ref "LED15") (pin "A") (pinfunction "A_A") (pintype "passive"))
    )
    (net (code "18") (name "Net-(LED16-C)") (class "Default")
      (node (ref "LED16") (pin "K") (pinfunction "C_K") (pintype "passive"))
      (node (ref "LED17") (pin "A") (pinfunction "A_A") (pintype "passive"))
    )
    (net (code "19") (name "Net-(LED16-PadA)") (class "Default")
      (node (ref "LED16") (pin "A") (pinfunction "A_A") (pintype "passive"))
      (node (ref "R6") (pin "2") (pinfunction "2_2") (pintype "passive"))
    )
    (net (code "20") (name "Net-(LED17-C)") (class "Default")
      (node (ref "LED17") (pin "K") (pinfunction "C_K") (pintype "passive"))
      (node (ref "LED18") (pin "A") (pinfunction "A_A") (pintype "passive"))
    )
    (net (code "21") (name "Net-(LED19-C)") (class "Default")
      (node (ref "LED19") (pin "K") (pinfunction "C_K") (pintype "passive"))
      (node (ref "LED20") (pin "A") (pinfunction "A_A") (pintype "passive"))
    )
    (net (code "22") (name "Net-(LED19-PadA)") (class "Default")
      (node (ref "LED19") (pin "A") (pinfunction "A_A") (pintype "passive"))
      (node (ref "R7") (pin "2") (pinfunction "2_2") (pintype "passive"))
    )
    (net (code "23") (name "Net-(LED20-C)") (class "Default")
      (node (ref "LED20") (pin "K") (pinfunction "C_K") (pintype "passive"))
      (node (ref "LED21") (pin "A") (pinfunction "A_A") (pintype "passive"))
    )
    (net (code "24") (name "Net-(LED22-C)") (class "Default")
      (node (ref "LED22") (pin "K") (pinfunction "C_K") (pintype "passive"))
      (node (ref "LED23") (pin "A") (pinfunction "A_A") (pintype "passive"))
    )
    (net (code "25") (name "Net-(LED22-PadA)") (class "Default")
      (node (ref "LED22") (pin "A") (pinfunction "A_A") (pintype "passive"))
      (node (ref "R8") (pin "2") (pinfunction "2_2") (pintype "passive"))
    )
    (net (code "26") (name "Net-(LED23-C)") (class "Default")
      (node (ref "LED23") (pin "K") (pinfunction "C_K") (pintype "passive"))
      (node (ref "LED24") (pin "A") (pinfunction "A_A") (pintype "passive"))
    )
    (net (code "27") (name "Net-(LED25-C)") (class "Default")
      (node (ref "LED25") (pin "K") (pinfunction "C_K") (pintype "passive"))
      (node (ref "LED26") (pin "A") (pinfunction "A_A") (pintype "passive"))
    )
    (net (code "28") (name "Net-(LED25-PadA)") (class "Default")
      (node (ref "LED25") (pin "A") (pinfunction "A_A") (pintype "passive"))
      (node (ref "R9") (pin "2") (pinfunction "2_2") (pintype "passive"))
    )
    (net (code "29") (name "Net-(LED26-C)") (class "Default")
      (node (ref "LED26") (pin "K") (pinfunction "C_K") (pintype "passive"))
      (node (ref "LED27") (pin "A") (pinfunction "A_A") (pintype "passive"))
    )
    (net (code "30") (name "Net-(LED28-C)") (class "Default")
      (node (ref "LED28") (pin "K") (pinfunction "C_K") (pintype "passive"))
      (node (ref "LED29") (pin "A") (pinfunction "A_A") (pintype "passive"))
    )
    (net (code "31") (name "Net-(LED28-PadA)") (class "Default")
      (node (ref "LED28") (pin "A") (pinfunction "A_A") (pintype "passive"))
      (node (ref "R10") (pin "2") (pinfunction "2_2") (pintype "passive"))
    )
    (net (code "32") (name "Net-(LED29-C)") (class "Default")
      (node (ref "LED29") (pin "K") (pinfunction "C_K") (pintype "passive"))
      (node (ref "LED30") (pin "A") (pinfunction "A_A") (pintype "passive"))
    )
    (net (code "33") (name "Net-(LED31-C)") (class "Default")
      (node (ref "LED31") (pin "K") (pinfunction "C_K") (pintype "passive"))
      (node (ref "LED32") (pin "A") (pinfunction "A_A") (pintype "passive"))
    )
    (net (code "34") (name "Net-(LED31-PadA)") (class "Default")
      (node (ref "LED31") (pin "A") (pinfunction "A_A") (pintype "passive"))
      (node (ref "R11") (pin "2") (pinfunction "2_2") (pintype "passive"))
    )
    (net (code "35") (name "Net-(LED32-C)") (class "Default")
      (node (ref "LED32") (pin "K") (pinfunction "C_K") (pintype "passive"))
      (node (ref "LED33") (pin "A") (pinfunction "A_A") (pintype "passive"))
    )
    (net (code "36") (name "Net-(LED34-C)") (class "Default")
      (node (ref "LED34") (pin "K") (pinfunction "C_K") (pintype "passive"))
      (node (ref "LED35") (pin "A") (pinfunction "A_A") (pintype "passive"))
    )
    (net (code "37") (name "Net-(LED34-PadA)") (class "Default")
      (node (ref "LED34") (pin "A") (pinfunction "A_A") (pintype "passive"))
      (node (ref "R12") (pin "2") (pinfunction "2_2") (pintype "passive"))
    )
    (net (code "38") (name "Net-(LED35-C)") (class "Default")
      (node (ref "LED35") (pin "K") (pinfunction "C_K") (pintype "passive"))
      (node (ref "LED36") (pin "A") (pinfunction "A_A") (pintype "passive"))
    )
    (net (code "39") (name "Net-(LED37-C)") (class "Default")
      (node (ref "LED37") (pin "K") (pinfunction "C_K") (pintype "passive"))
      (node (ref "LED38") (pin "A") (pinfunction "A_A") (pintype "passive"))
    )
    (net (code "40") (name "Net-(LED37-PadA)") (class "Default")
      (node (ref "LED37") (pin "A") (pinfunction "A_A") (pintype "passive"))
      (node (ref "R13") (pin "2") (pinfunction "2_2") (pintype "passive"))
    )
    (net (code "41") (name "Net-(LED38-C)") (class "Default")
      (node (ref "LED38") (pin "K") (pinfunction "C_K") (pintype "passive"))
      (node (ref "LED39") (pin "A") (pinfunction "A_A") (pintype "passive"))
    )
    (net (code "42") (name "Net-(LED40-C)") (class "Default")
      (node (ref "LED40") (pin "K") (pinfunction "C_K") (pintype "passive"))
      (node (ref "LED41") (pin "A") (pinfunction "A_A") (pintype "passive"))
    )
    (net (code "43") (name "Net-(LED40-PadA)") (class "Default")
      (node (ref "LED40") (pin "A") (pinfunction "A_A") (pintype "passive"))
      (node (ref "R14") (pin "2") (pinfunction "2_2") (pintype "passive"))
    )
    (net (code "44") (name "Net-(LED41-C)") (class "Default")
      (node (ref "LED41") (pin "K") (pinfunction "C_K") (pintype "passive"))
      (node (ref "LED42") (pin "A") (pinfunction "A_A") (pintype "passive"))
    )
    (net (code "45") (name "Net-(LED43-C)") (class "Default")
      (node (ref "LED43") (pin "K") (pinfunction "C_K") (pintype "passive"))
      (node (ref "LED44") (pin "A") (pinfunction "A_A") (pintype "passive"))
    )
    (net (code "46") (name "Net-(LED43-PadA)") (class "Default")
      (node (ref "LED43") (pin "A") (pinfunction "A_A") (pintype "passive"))
      (node (ref "R15") (pin "2") (pinfunction "2_2") (pintype "passive"))
    )
    (net (code "47") (name "Net-(LED44-C)") (class "Default")
      (node (ref "LED44") (pin "K") (pinfunction "C_K") (pintype "passive"))
      (node (ref "LED45") (pin "A") (pinfunction "A_A") (pintype "passive"))
    )
    (net (code "48") (name "Net-(LED46-C)") (class "Default")
      (node (ref "LED46") (pin "K") (pinfunction "C_K") (pintype "passive"))
      (node (ref "LED47") (pin "A") (pinfunction "A_A") (pintype "passive"))
    )
    (net (code "49") (name "Net-(LED46-PadA)") (class "Default")
      (node (ref "LED46") (pin "A") (pinfunction "A_A") (pintype "passive"))
      (node (ref "R16") (pin "2") (pinfunction "2_2") (pintype "passive"))
    )
    (net (code "50") (name "Net-(LED47-C)") (class "Default")
      (node (ref "LED47") (pin "K") (pinfunction "C_K") (pintype "passive"))
      (node (ref "LED48") (pin "A") (pinfunction "A_A") (pintype "passive"))
    )
    (net (code "51") (name "Net-(LED49-C)") (class "Default")
      (node (ref "LED49") (pin "K") (pinfunction "C_K") (pintype "passive"))
      (node (ref "LED50") (pin "A") (pinfunction "A_A") (pintype "passive"))
    )
    (net (code "52") (name "Net-(LED49-PadA)") (class "Default")
      (node (ref "LED49") (pin "A") (pinfunction "A_A") (pintype "passive"))
      (node (ref "R17") (pin "2") (pinfunction "2_2") (pintype "passive"))
    )
    (net (code "53") (name "Net-(LED50-C)") (class "Default")
      (node (ref "LED50") (pin "K") (pinfunction "C_K") (pintype "passive"))
      (node (ref "LED51") (pin "A") (pinfunction "A_A") (pintype "passive"))
    )
    (net (code "54") (name "Net-(LED52-C)") (class "Default")
      (node (ref "LED52") (pin "K") (pinfunction "C_K") (pintype "passive"))
      (node (ref "LED53") (pin "A") (pinfunction "A_A") (pintype "passive"))
    )
    (net (code "55") (name "Net-(LED52-PadA)") (class "Default")
      (node (ref "LED52") (pin "A") (pinfunction "A_A") (pintype "passive"))
      (node (ref "R18") (pin "2") (pinfunction "2_2") (pintype "passive"))
    )
    (net (code "56") (name "Net-(LED53-C)") (class "Default")
      (node (ref "LED53") (pin "K") (pinfunction "C_K") (pintype "passive"))
      (node (ref "LED54") (pin "A") (pinfunction "A_A") (pintype "passive"))
    )
    (net (code "57") (name "Net-(LED55-C)") (class "Default")
      (node (ref "LED55") (pin "K") (pinfunction "C_K") (pintype "passive"))
      (node (ref "LED56") (pin "A") (pinfunction "A_A") (pintype "passive"))
    )
    (net (code "58") (name "Net-(LED55-PadA)") (class "Default")
      (node (ref "LED55") (pin "A") (pinfunction "A_A") (pintype "passive"))
      (node (ref "R19") (pin "2") (pinfunction "2_2") (pintype "passive"))
    )
    (net (code "59") (name "Net-(LED56-C)") (class "Default")
      (node (ref "LED56") (pin "K") (pinfunction "C_K") (pintype "passive"))
      (node (ref "LED57") (pin "A") (pinfunction "A_A") (pintype "passive"))
    )
    (net (code "60") (name "Net-(LED58-C)") (class "Default")
      (node (ref "LED58") (pin "K") (pinfunction "C_K") (pintype "passive"))
      (node (ref "LED59") (pin "A") (pinfunction "A_A") (pintype "passive"))
    )
    (net (code "61") (name "Net-(LED58-PadA)") (class "Default")
      (node (ref "LED58") (pin "A") (pinfunction "A_A") (pintype "passive"))
      (node (ref "R20") (pin "2") (pinfunction "2_2") (pintype "passive"))
    )
    (net (code "62") (name "Net-(LED59-C)") (class "Default")
      (node (ref "LED59") (pin "K") (pinfunction "C_K") (pintype "passive"))
      (node (ref "LED60") (pin "A") (pinfunction "A_A") (pintype "passive"))
    )
    (net (code "63") (name "Net-(LED61-C)") (class "Default")
      (node (ref "LED61") (pin "K") (pinfunction "C_K") (pintype "passive"))
      (node (ref "LED62") (pin "A") (pinfunction "A_A") (pintype "passive"))
    )
    (net (code "64") (name "Net-(LED61-PadA)") (class "Default")
      (node (ref "LED61") (pin "A") (pinfunction "A_A") (pintype "passive"))
      (node (ref "R21") (pin "2") (pinfunction "2_2") (pintype "passive"))
    )
    (net (code "65") (name "Net-(LED62-C)") (class "Default")
      (node (ref "LED62") (pin "K") (pinfunction "C_K") (pintype "passive"))
      (node (ref "LED63") (pin "A") (pinfunction "A_A") (pintype "passive"))
    )
    (net (code "66") (name "Net-(LED64-C)") (class "Default")
      (node (ref "LED64") (pin "K") (pinfunction "C_K") (pintype "passive"))
      (node (ref "LED65") (pin "A") (pinfunction "A_A") (pintype "passive"))
    )
    (net (code "67") (name "Net-(LED64-PadA)") (class "Default")
      (node (ref "LED64") (pin "A") (pinfunction "A_A") (pintype "passive"))
      (node (ref "R22") (pin "2") (pinfunction "2_2") (pintype "passive"))
    )
    (net (code "68") (name "Net-(LED65-C)") (class "Default")
      (node (ref "LED65") (pin "K") (pinfunction "C_K") (pintype "passive"))
      (node (ref "LED66") (pin "A") (pinfunction "A_A") (pintype "passive"))
    )
    (net (code "69") (name "Net-(LED67-C)") (class "Default")
      (node (ref "LED67") (pin "K") (pinfunction "C_K") (pintype "passive"))
      (node (ref "LED68") (pin "A") (pinfunction "A_A") (pintype "passive"))
    )
    (net (code "70") (name "Net-(LED67-PadA)") (class "Default")
      (node (ref "LED67") (pin "A") (pinfunction "A_A") (pintype "passive"))
      (node (ref "R23") (pin "2") (pinfunction "2_2") (pintype "passive"))
    )
    (net (code "71") (name "Net-(LED68-C)") (class "Default")
      (node (ref "LED68") (pin "K") (pinfunction "C_K") (pintype "passive"))
      (node (ref "LED69") (pin "A") (pinfunction "A_A") (pintype "passive"))
    )
    (net (code "72") (name "Net-(LED70-C)") (class "Default")
      (node (ref "LED70") (pin "K") (pinfunction "C_K") (pintype "passive"))
      (node (ref "LED71") (pin "A") (pinfunction "A_A") (pintype "passive"))
    )
    (net (code "73") (name "Net-(LED70-PadA)") (class "Default")
      (node (ref "LED70") (pin "A") (pinfunction "A_A") (pintype "passive"))
      (node (ref "R24") (pin "2") (pinfunction "2_2") (pintype "passive"))
    )
    (net (code "74") (name "Net-(LED71-C)") (class "Default")
      (node (ref "LED71") (pin "K") (pinfunction "C_K") (pintype "passive"))
      (node (ref "LED72") (pin "A") (pinfunction "A_A") (pintype "passive"))
    )
    (net (code "75") (name "Net-(LED73-C)") (class "Default")
      (node (ref "LED73") (pin "K") (pinfunction "C_K") (pintype "passive"))
      (node (ref "LED74") (pin "A") (pinfunction "A_A") (pintype "passive"))
    )
    (net (code "76") (name "Net-(LED73-PadA)") (class "Default")
      (node (ref "LED73") (pin "A") (pinfunction "A_A") (pintype "passive"))
      (node (ref "R25") (pin "2") (pinfunction "2_2") (pintype "passive"))
    )
    (net (code "77") (name "Net-(LED74-C)") (class "Default")
      (node (ref "LED74") (pin "K") (pinfunction "C_K") (pintype "passive"))
      (node (ref "LED75") (pin "A") (pinfunction "A_A") (pintype "passive"))
    )
    (net (code "78") (name "Net-(LED76-C)") (class "Default")
      (node (ref "LED76") (pin "K") (pinfunction "C_K") (pintype "passive"))
      (node (ref "LED77") (pin "A") (pinfunction "A_A") (pintype "passive"))
    )
    (net (code "79") (name "Net-(LED76-PadA)") (class "Default")
      (node (ref "LED76") (pin "A") (pinfunction "A_A") (pintype "passive"))
      (node (ref "R26") (pin "2") (pinfunction "2_2") (pintype "passive"))
    )
    (net (code "80") (name "Net-(LED77-C)") (class "Default")
      (node (ref "LED77") (pin "K") (pinfunction "C_K") (pintype "passive"))
      (node (ref "LED78") (pin "A") (pinfunction "A_A") (pintype "passive"))
    )
    (net (code "81") (name "Net-(LED79-C)") (class "Default")
      (node (ref "LED79") (pin "K") (pinfunction "C_K") (pintype "passive"))
      (node (ref "LED80") (pin "A") (pinfunction "A_A") (pintype "passive"))
    )
    (net (code "82") (name "Net-(LED79-PadA)") (class "Default")
      (node (ref "LED79") (pin "A") (pinfunction "A_A") (pintype "passive"))
      (node (ref "R27") (pin "2") (pinfunction "2_2") (pintype "passive"))
    )
    (net (code "83") (name "Net-(LED80-C)") (class "Default")
      (node (ref "LED80") (pin "K") (pinfunction "C_K") (pintype "passive"))
      (node (ref "LED81") (pin "A") (pinfunction "A_A") (pintype "passive"))
    )
    (net (code "84") (name "Net-(LED82-C)") (class "Default")
      (node (ref "LED82") (pin "K") (pinfunction "C_K") (pintype "passive"))
      (node (ref "LED83") (pin "A") (pinfunction "A_A") (pintype "passive"))
    )
    (net (code "85") (name "Net-(LED82-PadA)") (class "Default")
      (node (ref "LED82") (pin "A") (pinfunction "A_A") (pintype "passive"))
      (node (ref "R28") (pin "2") (pinfunction "2_2") (pintype "passive"))
    )
    (net (code "86") (name "Net-(LED83-C)") (class "Default")
      (node (ref "LED83") (pin "K") (pinfunction "C_K") (pintype "passive"))
      (node (ref "LED84") (pin "A") (pinfunction "A_A") (pintype "passive"))
    )
    (net (code "87") (name "Net-(LED85-C)") (class "Default")
      (node (ref "LED85") (pin "K") (pinfunction "C_K") (pintype "passive"))
      (node (ref "LED86") (pin "A") (pinfunction "A_A") (pintype "passive"))
    )
    (net (code "88") (name "Net-(LED85-PadA)") (class "Default")
      (node (ref "LED85") (pin "A") (pinfunction "A_A") (pintype "passive"))
      (node (ref "R29") (pin "2") (pinfunction "2_2") (pintype "passive"))
    )
    (net (code "89") (name "Net-(LED86-C)") (class "Default")
      (node (ref "LED86") (pin "K") (pinfunction "C_K") (pintype "passive"))
      (node (ref "LED87") (pin "A") (pinfunction "A_A") (pintype "passive"))
    )
    (net (code "90") (name "Net-(LED88-C)") (class "Default")
      (node (ref "LED88") (pin "K") (pinfunction "C_K") (pintype "passive"))
      (node (ref "LED89") (pin "A") (pinfunction "A_A") (pintype "passive"))
    )
    (net (code "91") (name "Net-(LED88-PadA)") (class "Default")
      (node (ref "LED88") (pin "A") (pinfunction "A_A") (pintype "passive"))
      (node (ref "R30") (pin "2") (pinfunction "2_2") (pintype "passive"))
    )
    (net (code "92") (name "Net-(LED89-C)") (class "Default")
      (node (ref "LED89") (pin "K") (pinfunction "C_K") (pintype "passive"))
      (node (ref "LED90") (pin "A") (pinfunction "A_A") (pintype "passive"))
    )
    (net (code "93") (name "Net-(LED91-C)") (class "Default")
      (node (ref "LED91") (pin "K") (pinfunction "C_K") (pintype "passive"))
      (node (ref "LED92") (pin "A") (pinfunction "A_A") (pintype "passive"))
    )
    (net (code "94") (name "Net-(LED91-PadA)") (class "Default")
      (node (ref "LED91") (pin "A") (pinfunction "A_A") (pintype "passive"))
      (node (ref "R31") (pin "2") (pinfunction "2_2") (pintype "passive"))
    )
    (net (code "95") (name "Net-(LED92-C)") (class "Default")
      (node (ref "LED92") (pin "K") (pinfunction "C_K") (pintype "passive"))
      (node (ref "LED93") (pin "A") (pinfunction "A_A") (pintype "passive"))
    )
    (net (code "96") (name "Net-(LED94-C)") (class "Default")
      (node (ref "LED94") (pin "K") (pinfunction "C_K") (pintype "passive"))
      (node (ref "LED95") (pin "A") (pinfunction "A_A") (pintype "passive"))
    )
    (net (code "97") (name "Net-(LED94-PadA)") (class "Default")
      (node (ref "LED94") (pin "A") (pinfunction "A_A") (pintype "passive"))
      (node (ref "R32") (pin "2") (pinfunction "2_2") (pintype "passive"))
    )
    (net (code "98") (name "Net-(LED95-C)") (class "Default")
      (node (ref "LED95") (pin "K") (pinfunction "C_K") (pintype "passive"))
      (node (ref "LED96") (pin "A") (pinfunction "A_A") (pintype "passive"))
    )
    (net (code "99") (name "Net-(LED97-C)") (class "Default")
      (node (ref "LED97") (pin "K") (pinfunction "C_K") (pintype "passive"))
      (node (ref "LED98") (pin "A") (pinfunction "A_A") (pintype "passive"))
    )
    (net (code "100") (name "Net-(LED97-PadA)") (class "Default")
      (node (ref "LED97") (pin "A") (pinfunction "A_A") (pintype "passive"))
      (node (ref "R33") (pin "2") (pinfunction "2_2") (pintype "passive"))
    )
    (net (code "101") (name "Net-(LED98-C)") (class "Default")
      (node (ref "LED98") (pin "K") (pinfunction "C_K") (pintype "passive"))
      (node (ref "LED99") (pin "A") (pinfunction "A_A") (pintype "passive"))
    )
    (net (code "102") (name "Net-(LED100-C)") (class "Default")
      (node (ref "LED100") (pin "K") (pinfunction "C_K") (pintype "passive"))
      (node (ref "LED101") (pin "A") (pinfunction "A_A") (pintype "passive"))
    )
    (net (code "103") (name "Net-(LED100-PadA)") (class "Default")
      (node (ref "LED100") (pin "A") (pinfunction "A_A") (pintype "passive"))
      (node (ref "R34") (pin "2") (pinfunction "2_2") (pintype "passive"))
    )
    (net (code "104") (name "Net-(LED101-C)") (class "Default")
      (node (ref "LED101") (pin "K") (pinfunction "C_K") (pintype "passive"))
      (node (ref "LED102") (pin "A") (pinfunction "A_A") (pintype "passive"))
    )
    (net (code "105") (name "Net-(LED103-C)") (class "Default")
      (node (ref "LED103") (pin "K") (pinfunction "C_K") (pintype "passive"))
      (node (ref "LED104") (pin "A") (pinfunction "A_A") (pintype "passive"))
    )
    (net (code "106") (name "Net-(LED103-PadA)") (class "Default")
      (node (ref "LED103") (pin "A") (pinfunction "A_A") (pintype "passive"))
      (node (ref "R35") (pin "2") (pinfunction "2_2") (pintype "passive"))
    )
    (net (code "107") (name "Net-(LED104-C)") (class "Default")
      (node (ref "LED104") (pin "K") (pinfunction "C_K") (pintype "passive"))
      (node (ref "LED105") (pin "A") (pinfunction "A_A") (pintype "passive"))
    )
    (net (code "108") (name "Net-(LED106-C)") (class "Default")
      (node (ref "LED106") (pin "K") (pinfunction "C_K") (pintype "passive"))
      (node (ref "LED107") (pin "A") (pinfunction "A_A") (pintype "passive"))
    )
    (net (code "109") (name "Net-(LED106-PadA)") (class "Default")
      (node (ref "LED106") (pin "A") (pinfunction "A_A") (pintype "passive"))
      (node (ref "R36") (pin "2") (pinfunction "2_2") (pintype "passive"))
    )
    (net (code "110") (name "Net-(LED107-C)") (class "Default")
      (node (ref "LED107") (pin "K") (pinfunction "C_K") (pintype "passive"))
      (node (ref "LED108") (pin "A") (pinfunction "A_A") (pintype "passive"))
    )
    (net (code "111") (name "Net-(LED109-C)") (class "Default")
      (node (ref "LED109") (pin "K") (pinfunction "C_K") (pintype "passive"))
      (node (ref "LED110") (pin "A") (pinfunction "A_A") (pintype "passive"))
    )
    (net (code "112") (name "Net-(LED109-PadA)") (class "Default")
      (node (ref "LED109") (pin "A") (pinfunction "A_A") (pintype "passive"))
      (node (ref "R37") (pin "2") (pinfunction "2_2") (pintype "passive"))
    )
    (net (code "113") (name "Net-(LED110-C)") (class "Default")
      (node (ref "LED110") (pin "K") (pinfunction "C_K") (pintype "passive"))
      (node (ref "LED111") (pin "A") (pinfunction "A_A") (pintype "passive"))
    )
    (net (code "114") (name "Net-(LED112-C)") (class "Default")
      (node (ref "LED112") (pin "K") (pinfunction "C_K") (pintype "passive"))
      (node (ref "LED113") (pin "A") (pinfunction "A_A") (pintype "passive"))
    )
    (net (code "115") (name "Net-(LED112-PadA)") (class "Default")
      (node (ref "LED112") (pin "A") (pinfunction "A_A") (pintype "passive"))
      (node (ref "R38") (pin "2") (pinfunction "2_2") (pintype "passive"))
    )
    (net (code "116") (name "Net-(LED113-C)") (class "Default")
      (node (ref "LED113") (pin "K") (pinfunction "C_K") (pintype "passive"))
      (node (ref "LED114") (pin "A") (pinfunction "A_A") (pintype "passive"))
    )
    (net (code "117") (name "Net-(LED115-C)") (class "Default")
      (node (ref "LED115") (pin "K") (pinfunction "C_K") (pintype "passive"))
      (node (ref "LED116") (pin "A") (pinfunction "A_A") (pintype "passive"))
    )
    (net (code "118") (name "Net-(LED115-PadA)") (class "Default")
      (node (ref "LED115") (pin "A") (pinfunction "A_A") (pintype "passive"))
      (node (ref "R39") (pin "2") (pinfunction "2_2") (pintype "passive"))
    )
    (net (code "119") (name "Net-(LED116-C)") (class "Default")
      (node (ref "LED116") (pin "K") (pinfunction "C_K") (pintype "passive"))
      (node (ref "LED117") (pin "A") (pinfunction "A_A") (pintype "passive"))
    )
    (net (code "120") (name "Net-(LED118-C)") (class "Default")
      (node (ref "LED118") (pin "K") (pinfunction "C_K") (pintype "passive"))
      (node (ref "LED119") (pin "A") (pinfunction "A_A") (pintype "passive"))
    )
    (net (code "121") (name "Net-(LED118-PadA)") (class "Default")
      (node (ref "LED118") (pin "A") (pinfunction "A_A") (pintype "passive"))
      (node (ref "R40") (pin "2") (pinfunction "2_2") (pintype "passive"))
    )
    (net (code "122") (name "Net-(LED119-C)") (class "Default")
      (node (ref "LED119") (pin "K") (pinfunction "C_K") (pintype "passive"))
      (node (ref "LED120") (pin "A") (pinfunction "A_A") (pintype "passive"))
    )
    (net (code "123") (name "Net-(LED121-C)") (class "Default")
      (node (ref "LED121") (pin "K") (pinfunction "C_K") (pintype "passive"))
      (node (ref "LED122") (pin "A") (pinfunction "A_A") (pintype "passive"))
    )
    (net (code "124") (name "Net-(LED121-PadA)") (class "Default")
      (node (ref "LED121") (pin "A") (pinfunction "A_A") (pintype "passive"))
      (node (ref "R41") (pin "2") (pinfunction "2_2") (pintype "passive"))
    )
    (net (code "125") (name "Net-(LED122-C)") (class "Default")
      (node (ref "LED122") (pin "K") (pinfunction "C_K") (pintype "passive"))
      (node (ref "LED123") (pin "A") (pinfunction "A_A") (pintype "passive"))
    )
    (net (code "126") (name "Net-(LED124-C)") (class "Default")
      (node (ref "LED124") (pin "K") (pinfunction "C_K") (pintype "passive"))
      (node (ref "LED125") (pin "A") (pinfunction "A_A") (pintype "passive"))
    )
    (net (code "127") (name "Net-(LED124-PadA)") (class "Default")
      (node (ref "LED124") (pin "A") (pinfunction "A_A") (pintype "passive"))
      (node (ref "R42") (pin "2") (pinfunction "2_2") (pintype "passive"))
    )
    (net (code "128") (name "Net-(LED125-C)") (class "Default")
      (node (ref "LED125") (pin "K") (pinfunction "C_K") (pintype "passive"))
      (node (ref "LED126") (pin "A") (pinfunction "A_A") (pintype "passive"))
    )
    (net (code "129") (name "Net-(LED127-C)") (class "Default")
      (node (ref "LED127") (pin "K") (pinfunction "C_K") (pintype "passive"))
      (node (ref "LED128") (pin "A") (pinfunction "A_A") (pintype "passive"))
    )
    (net (code "130") (name "Net-(LED127-PadA)") (class "Default")
      (node (ref "LED127") (pin "A") (pinfunction "A_A") (pintype "passive"))
      (node (ref "R43") (pin "2") (pinfunction "2_2") (pintype "passive"))
    )
    (net (code "131") (name "Net-(LED128-C)") (class "Default")
      (node (ref "LED128") (pin "K") (pinfunction "C_K") (pintype "passive"))
      (node (ref "LED129") (pin "A") (pinfunction "A_A") (pintype "passive"))
    )
    (net (code "132") (name "Net-(LED130-C)") (class "Default")
      (node (ref "LED130") (pin "K") (pinfunction "C_K") (pintype "passive"))
      (node (ref "LED131") (pin "A") (pinfunction "A_A") (pintype "passive"))
    )
    (net (code "133") (name "Net-(LED130-PadA)") (class "Default")
      (node (ref "LED130") (pin "A") (pinfunction "A_A") (pintype "passive"))
      (node (ref "R44") (pin "2") (pinfunction "2_2") (pintype "passive"))
    )
    (net (code "134") (name "Net-(LED131-C)") (class "Default")
      (node (ref "LED131") (pin "K") (pinfunction "C_K") (pintype "passive"))
      (node (ref "LED132") (pin "A") (pinfunction "A_A") (pintype "passive"))
    )
    (net (code "135") (name "Net-(LED133-C)") (class "Default")
      (node (ref "LED133") (pin "K") (pinfunction "C_K") (pintype "passive"))
      (node (ref "LED134") (pin "A") (pinfunction "A_A") (pintype "passive"))
    )
    (net (code "136") (name "Net-(LED133-PadA)") (class "Default")
      (node (ref "LED133") (pin "A") (pinfunction "A_A") (pintype "passive"))
      (node (ref "R45") (pin "2") (pinfunction "2_2") (pintype "passive"))
    )
    (net (code "137") (name "Net-(LED134-C)") (class "Default")
      (node (ref "LED134") (pin "K") (pinfunction "C_K") (pintype "passive"))
      (node (ref "LED135") (pin "A") (pinfunction "A_A") (pintype "passive"))
    )
    (net (code "138") (name "Net-(LED136-C)") (class "Default")
      (node (ref "LED136") (pin "K") (pinfunction "C_K") (pintype "passive"))
      (node (ref "LED137") (pin "A") (pinfunction "A_A") (pintype "passive"))
    )
    (net (code "139") (name "Net-(LED136-PadA)") (class "Default")
      (node (ref "LED136") (pin "A") (pinfunction "A_A") (pintype "passive"))
      (node (ref "R46") (pin "2") (pinfunction "2_2") (pintype "passive"))
    )
    (net (code "140") (name "Net-(LED137-C)") (class "Default")
      (node (ref "LED137") (pin "K") (pinfunction "C_K") (pintype "passive"))
      (node (ref "LED138") (pin "A") (pinfunction "A_A") (pintype "passive"))
    )
    (net (code "141") (name "Net-(LED139-C)") (class "Default")
      (node (ref "LED139") (pin "K") (pinfunction "C_K") (pintype "passive"))
      (node (ref "LED140") (pin "A") (pinfunction "A_A") (pintype "passive"))
    )
    (net (code "142") (name "Net-(LED139-PadA)") (class "Default")
      (node (ref "LED139") (pin "A") (pinfunction "A_A") (pintype "passive"))
      (node (ref "R47") (pin "2") (pinfunction "2_2") (pintype "passive"))
    )
    (net (code "143") (name "Net-(LED140-C)") (class "Default")
      (node (ref "LED140") (pin "K") (pinfunction "C_K") (pintype "passive"))
      (node (ref "LED141") (pin "A") (pinfunction "A_A") (pintype "passive"))
    )
    (net (code "144") (name "Net-(LED142-C)") (class "Default")
      (node (ref "LED142") (pin "K") (pinfunction "C_K") (pintype "passive"))
      (node (ref "LED143") (pin "A") (pinfunction "A_A") (pintype "passive"))
    )
    (net (code "145") (name "Net-(LED142-PadA)") (class "Default")
      (node (ref "LED142") (pin "A") (pinfunction "A_A") (pintype "passive"))
      (node (ref "R48") (pin "2") (pinfunction "2_2") (pintype "passive"))
    )
    (net (code "146") (name "Net-(LED143-C)") (class "Default")
      (node (ref "LED143") (pin "K") (pinfunction "C_K") (pintype "passive"))
      (node (ref "LED144") (pin "A") (pinfunction "A_A") (pintype "passive"))
    )
    (net (code "147") (name "Net-(LED145-C)") (class "Default")
      (node (ref "LED145") (pin "K") (pinfunction "C_K") (pintype "passive"))
      (node (ref "LED146") (pin "A") (pinfunction "A_A") (pintype "passive"))
    )
    (net (code "148") (name "Net-(LED145-PadA)") (class "Default")
      (node (ref "LED145") (pin "A") (pinfunction "A_A") (pintype "passive"))
      (node (ref "R49") (pin "2") (pinfunction "2_2") (pintype "passive"))
    )
    (net (code "149") (name "Net-(LED146-C)") (class "Default")
      (node (ref "LED146") (pin "K") (pinfunction "C_K") (pintype "passive"))
      (node (ref "LED147") (pin "A") (pinfunction "A_A") (pintype "passive"))
    )
    (net (code "150") (name "Net-(LED148-C)") (class "Default")
      (node (ref "LED148") (pin "K") (pinfunction "C_K") (pintype "passive"))
      (node (ref "LED149") (pin "A") (pinfunction "A_A") (pintype "passive"))
    )
    (net (code "151") (name "Net-(LED148-PadA)") (class "Default")
      (node (ref "LED148") (pin "A") (pinfunction "A_A") (pintype "passive"))
      (node (ref "R50") (pin "2") (pinfunction "2_2") (pintype "passive"))
    )
    (net (code "152") (name "Net-(LED149-C)") (class "Default")
      (node (ref "LED149") (pin "K") (pinfunction "C_K") (pintype "passive"))
      (node (ref "LED150") (pin "A") (pinfunction "A_A") (pintype "passive"))
    )
    (net (code "153") (name "unconnected-(X1B-S-Pad2)") (class "Default")
      (node (ref "X1") (pin "2") (pinfunction "S_2") (pintype "passive"))
    )
  )
)
